# Main.net
KiCad netlist of a schematic drawn in Altium Designer
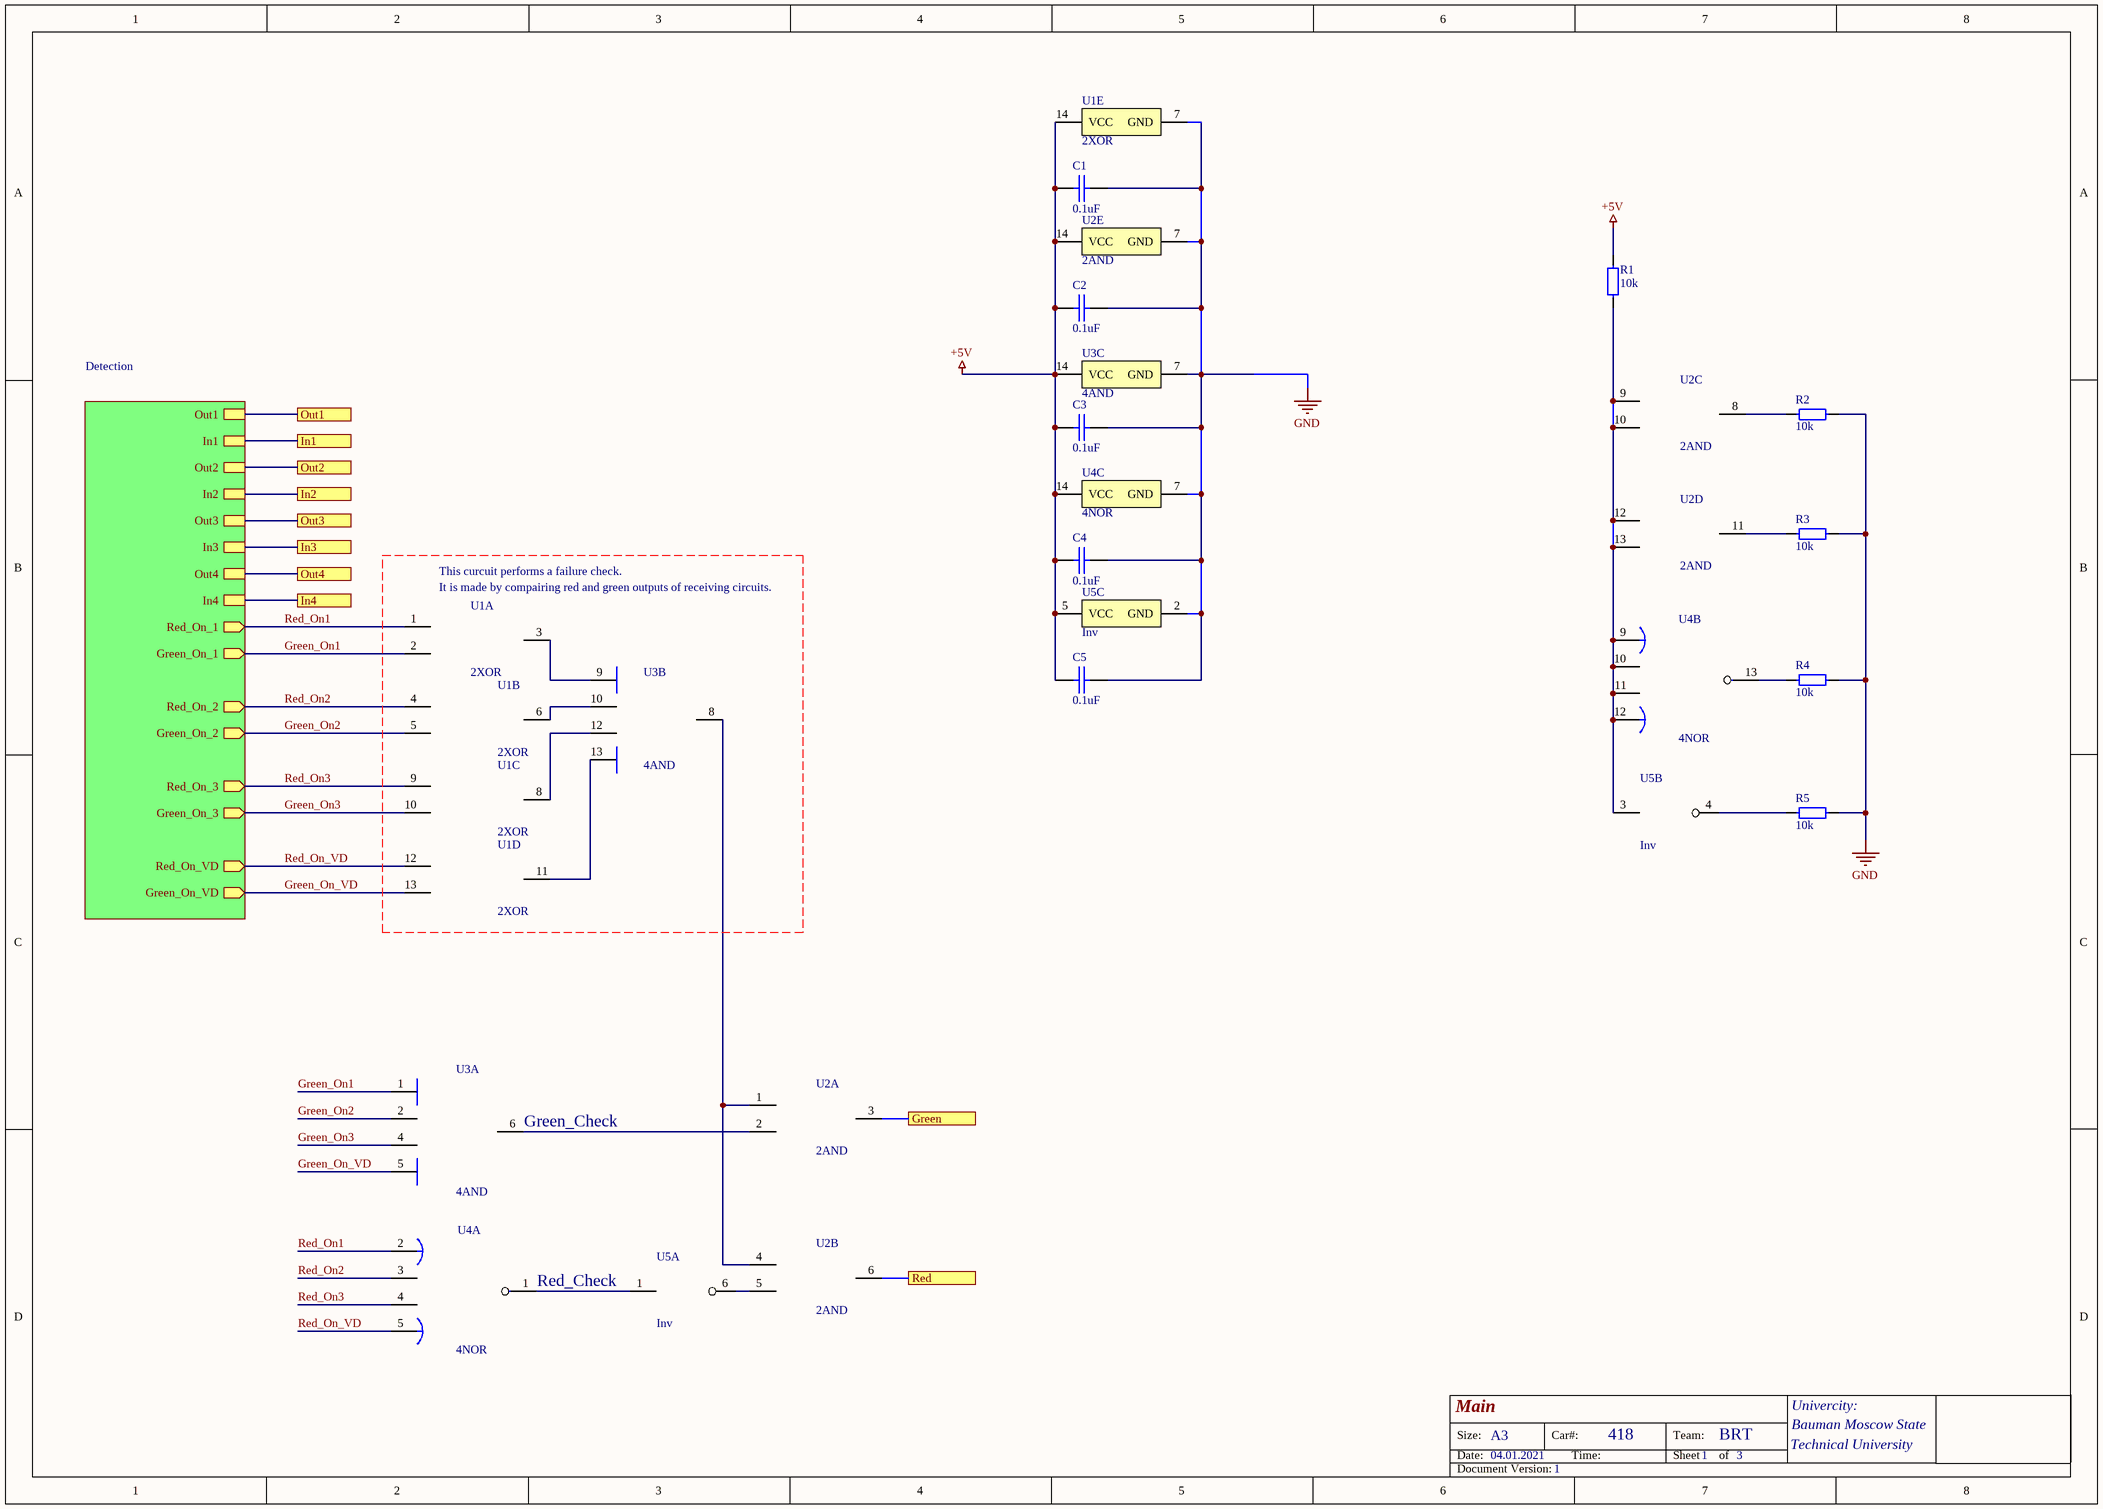
[diagram p0: Main.SchDoc]

(export (version "E")
  (design (tool "Eeschema 10.0.6"))
  (components
    (comp (ref "C1")
      (value "0.1uF")
      (footprint "0603 Capicator")
      (description "0.1uF X7R 16V 10% 0603")
      (fields
        (field (name "MANUFACTURER") "Murata Manufacturing")
        (field (name "PART NUMBER") "GRM188R71C104KA01D")
      )
      (libsource (lib "BRT_Components") (part "Cap 0.1uF (0603)"))
    )
    (comp (ref "C2")
      (value "0.1uF")
      (footprint "0603 Capicator")
      (description "0.1uF X7R 16V 10% 0603")
      (fields
        (field (name "MANUFACTURER") "Murata Manufacturing")
        (field (name "PART NUMBER") "GRM188R71C104KA01D")
      )
      (libsource (lib "BRT_Components") (part "Cap 0.1uF (0603)"))
    )
    (comp (ref "C3")
      (value "0.1uF")
      (footprint "0603 Capicator")
      (description "0.1uF X7R 16V 10% 0603")
      (fields
        (field (name "MANUFACTURER") "Murata Manufacturing")
        (field (name "PART NUMBER") "GRM188R71C104KA01D")
      )
      (libsource (lib "BRT_Components") (part "Cap 0.1uF (0603)"))
    )
    (comp (ref "C4")
      (value "0.1uF")
      (footprint "0603 Capicator")
      (description "0.1uF X7R 16V 10% 0603")
      (fields
        (field (name "MANUFACTURER") "Murata Manufacturing")
        (field (name "PART NUMBER") "GRM188R71C104KA01D")
      )
      (libsource (lib "BRT_Components") (part "Cap 0.1uF (0603)"))
    )
    (comp (ref "C5")
      (value "0.1uF")
      (footprint "0603 Capicator")
      (description "0.1uF X7R 16V 10% 0603")
      (fields
        (field (name "MANUFACTURER") "Murata Manufacturing")
        (field (name "PART NUMBER") "GRM188R71C104KA01D")
      )
      (libsource (lib "BRT_Components") (part "Cap 0.1uF (0603)"))
    )
    (comp (ref "R1")
      (value "10k")
      (footprint "0603 Resistor")
      (description "0.1W 0603 10k, 1%")
      (fields (field (name "PART NUMBER") "RC0603FR-0710KL") (field (name "MANUFACTURER") "Taiwan"))
      (libsource (lib "BRT_Components") (part "Res 10k (0603)"))
    )
    (comp (ref "R2")
      (value "10k")
      (footprint "0603 Resistor")
      (description "0.1W 0603 10k, 1%")
      (fields (field (name "PART NUMBER") "RC0603FR-0710KL") (field (name "MANUFACTURER") "Taiwan"))
      (libsource (lib "BRT_Components") (part "Res 10k (0603)"))
    )
    (comp (ref "R3")
      (value "10k")
      (footprint "0603 Resistor")
      (description "0.1W 0603 10k, 1%")
      (fields (field (name "PART NUMBER") "RC0603FR-0710KL") (field (name "MANUFACTURER") "Taiwan"))
      (libsource (lib "BRT_Components") (part "Res 10k (0603)"))
    )
    (comp (ref "R4")
      (value "10k")
      (footprint "0603 Resistor")
      (description "0.1W 0603 10k, 1%")
      (fields (field (name "PART NUMBER") "RC0603FR-0710KL") (field (name "MANUFACTURER") "Taiwan"))
      (libsource (lib "BRT_Components") (part "Res 10k (0603)"))
    )
    (comp (ref "R5")
      (value "10k")
      (footprint "0603 Resistor")
      (description "0.1W 0603 10k, 1%")
      (fields (field (name "PART NUMBER") "RC0603FR-0710KL") (field (name "MANUFACTURER") "Taiwan"))
      (libsource (lib "BRT_Components") (part "Res 10k (0603)"))
    )
    (comp (ref "U1")
      (value "2XOR")
      (footprint "SOIC-14")
      (description "4 logic elements \"2XOR\"")
      (fields (field (name "PART NUMBER") "74HC86D,653") (field (name "MANUFACTURER") "Nexperia"))
      (libsource (lib "BRT_Components") (part "4(2XOR)"))
    )
    (comp (ref "U2")
      (value "2AND")
      (footprint "SOIC-14")
      (description "4 logic elements \"2AND\"")
      (fields (field (name "PART NUMBER") "SN74AC08DR") (field (name "MANUFACTURER") "Texas Instruments"))
      (libsource (lib "BRT_Components") (part "2And"))
    )
    (comp (ref "U3")
      (value "4AND")
      (footprint "SOIC-14")
      (description "2 logic elements \"4AND\"")
      (fields (field (name "PART NUMBER") "74HC21D,653") (field (name "MANUFACTURER") "Nexperia"))
      (libsource (lib "BRT_Components") (part "2(4AND)"))
    )
    (comp (ref "U4")
      (value "4NOR")
      (footprint "SOIC-14")
      (description "2 logic elements \"4NOR\"")
      (fields (field (name "PART NUMBER") "74HC4002D,652") (field (name "MANUFACTURER") "Nexperia"))
      (libsource (lib "BRT_Components") (part "2(4NOR)"))
    )
    (comp (ref "U5")
      (value "Inv")
      (footprint "SOT236")
      (description "Dual inverter, 1.65-5.5V")
      (fields
        (field (name "MANUFACTURER") "Texas Instruments")
        (field (name "PART NUMBER") "SN74LVC2G04DBVR")
      )
      (libsource (lib "BRT_Components") (part "Inverter (SN74)"))
    )
  )
  (nets
    (net (code "1") (name "+5V") (class "Default")
      (node (ref "C1") (pin "2") (pinfunction "2_2") (pintype "passive"))
      (node (ref "C2") (pin "2") (pinfunction "2_2") (pintype "passive"))
      (node (ref "C3") (pin "2") (pinfunction "2_2") (pintype "passive"))
      (node (ref "C4") (pin "2") (pinfunction "2_2") (pintype "passive"))
      (node (ref "C5") (pin "2") (pinfunction "2_2") (pintype "passive"))
      (node (ref "R1") (pin "2") (pinfunction "2_2") (pintype "passive"))
      (node (ref "U1") (pin "14") (pinfunction "VCC_14") (pintype "passive"))
      (node (ref "U2") (pin "14") (pinfunction "VCC_14") (pintype "power_in"))
      (node (ref "U3") (pin "14") (pinfunction "VCC_14") (pintype "passive"))
      (node (ref "U4") (pin "14") (pinfunction "VCC_14") (pintype "passive"))
      (node (ref "U5") (pin "5") (pinfunction "VCC_5") (pintype "power_in"))
    )
    (net (code "2") (name "/Green") (class "Default")
      (node (ref "U2") (pin "3") (pinfunction "1Y_3") (pintype "passive"))
    )
    (net (code "3") (name "/Green_On1") (class "Default")
      (node (ref "U1") (pin "2") (pinfunction "B_2") (pintype "passive"))
      (node (ref "U3") (pin "1") (pinfunction "A_1") (pintype "passive"))
    )
    (net (code "4") (name "/Green_On2") (class "Default")
      (node (ref "U1") (pin "5") (pinfunction "B_5") (pintype "passive"))
      (node (ref "U3") (pin "2") (pinfunction "B_2") (pintype "passive"))
    )
    (net (code "5") (name "/Green_On3") (class "Default")
      (node (ref "U1") (pin "10") (pinfunction "B_10") (pintype "passive"))
      (node (ref "U3") (pin "4") (pinfunction "C_4") (pintype "passive"))
    )
    (net (code "6") (name "/Green_On_VD") (class "Default")
      (node (ref "U1") (pin "13") (pinfunction "B_13") (pintype "passive"))
      (node (ref "U3") (pin "5") (pinfunction "D_5") (pintype "passive"))
    )
    (net (code "15") (name "/Red") (class "Default")
      (node (ref "U2") (pin "6") (pinfunction "2Y_6") (pintype "passive"))
    )
    (net (code "16") (name "/Red_On1") (class "Default")
      (node (ref "U1") (pin "1") (pinfunction "A_1") (pintype "passive"))
      (node (ref "U4") (pin "2") (pinfunction "A_2") (pintype "passive"))
    )
    (net (code "17") (name "/Red_On2") (class "Default")
      (node (ref "U1") (pin "4") (pinfunction "A_4") (pintype "passive"))
      (node (ref "U4") (pin "3") (pinfunction "B_3") (pintype "passive"))
    )
    (net (code "18") (name "/Red_On3") (class "Default")
      (node (ref "U1") (pin "9") (pinfunction "A_9") (pintype "passive"))
      (node (ref "U4") (pin "4") (pinfunction "C_4") (pintype "passive"))
    )
    (net (code "19") (name "/Red_On_VD") (class "Default")
      (node (ref "U1") (pin "12") (pinfunction "A_12") (pintype "passive"))
      (node (ref "U4") (pin "5") (pinfunction "D_5") (pintype "passive"))
    )
    (net (code "20") (name "GND") (class "Default")
      (node (ref "C1") (pin "1") (pinfunction "1_1") (pintype "passive"))
      (node (ref "C2") (pin "1") (pinfunction "1_1") (pintype "passive"))
      (node (ref "C3") (pin "1") (pinfunction "1_1") (pintype "passive"))
      (node (ref "C4") (pin "1") (pinfunction "1_1") (pintype "passive"))
      (node (ref "C5") (pin "1") (pinfunction "1_1") (pintype "passive"))
      (node (ref "R2") (pin "1") (pinfunction "1_1") (pintype "passive"))
      (node (ref "R3") (pin "1") (pinfunction "1_1") (pintype "passive"))
      (node (ref "R4") (pin "1") (pinfunction "1_1") (pintype "passive"))
      (node (ref "R5") (pin "1") (pinfunction "1_1") (pintype "passive"))
      (node (ref "U1") (pin "7") (pinfunction "GND_7") (pintype "passive"))
      (node (ref "U2") (pin "7") (pinfunction "GND_7") (pintype "power_in"))
      (node (ref "U3") (pin "7") (pinfunction "GND_7") (pintype "passive"))
      (node (ref "U4") (pin "7") (pinfunction "GND_7") (pintype "passive"))
      (node (ref "U5") (pin "2") (pinfunction "GND_2") (pintype "power_in"))
    )
    (net (code "21") (name "Net-(U1A-Y)") (class "Default")
      (node (ref "U1") (pin "3") (pinfunction "Y_3") (pintype "passive"))
      (node (ref "U3") (pin "9") (pinfunction "A_9") (pintype "passive"))
    )
    (net (code "22") (name "Net-(U1B-Y)") (class "Default")
      (node (ref "U1") (pin "6") (pinfunction "Y_6") (pintype "passive"))
      (node (ref "U3") (pin "10") (pinfunction "B_10") (pintype "passive"))
    )
    (net (code "23") (name "Net-(U1C-Y)") (class "Default")
      (node (ref "U1") (pin "8") (pinfunction "Y_8") (pintype "passive"))
      (node (ref "U3") (pin "12") (pinfunction "C_12") (pintype "passive"))
    )
    (net (code "24") (name "Net-(U1D-Y)") (class "Default")
      (node (ref "U1") (pin "11") (pinfunction "Y_11") (pintype "passive"))
      (node (ref "U3") (pin "13") (pinfunction "D_13") (pintype "passive"))
    )
    (net (code "25") (name "Net-(U2A-1A)") (class "Default")
      (node (ref "U2") (pin "1") (pinfunction "1A_1") (pintype "passive"))
      (node (ref "U2") (pin "4") (pinfunction "2A_4") (pintype "passive"))
      (node (ref "U3") (pin "8") (pinfunction "Y_8") (pintype "passive"))
    )
    (net (code "26") (name "Net-(U2A-1B)") (class "Default")
      (node (ref "U2") (pin "2") (pinfunction "1B_2") (pintype "passive"))
      (node (ref "U3") (pin "6") (pinfunction "Y_6") (pintype "passive"))
    )
    (net (code "27") (name "Net-(U2B-2B)") (class "Default")
      (node (ref "U2") (pin "5") (pinfunction "2B_5") (pintype "passive"))
      (node (ref "U5") (pin "6") (pinfunction "1Y_6") (pintype "passive"))
    )
    (net (code "28") (name "Net-(U2C-3A)") (class "Default")
      (node (ref "R1") (pin "1") (pinfunction "1_1") (pintype "passive"))
      (node (ref "U2") (pin "10") (pinfunction "3B_10") (pintype "passive"))
      (node (ref "U2") (pin "12") (pinfunction "4A_12") (pintype "passive"))
      (node (ref "U2") (pin "13") (pinfunction "4B_13") (pintype "passive"))
      (node (ref "U2") (pin "9") (pinfunction "3A_9") (pintype "passive"))
      (node (ref "U4") (pin "10") (pinfunction "B_10") (pintype "passive"))
      (node (ref "U4") (pin "11") (pinfunction "C_11") (pintype "passive"))
      (node (ref "U4") (pin "12") (pinfunction "D_12") (pintype "passive"))
      (node (ref "U4") (pin "9") (pinfunction "A_9") (pintype "passive"))
      (node (ref "U5") (pin "3") (pinfunction "2А_3") (pintype "passive"))
    )
    (net (code "29") (name "Net-(U2C-3Y)") (class "Default")
      (node (ref "R2") (pin "2") (pinfunction "2_2") (pintype "passive"))
      (node (ref "U2") (pin "8") (pinfunction "3Y_8") (pintype "passive"))
    )
    (net (code "30") (name "Net-(U2D-4Y)") (class "Default")
      (node (ref "R3") (pin "2") (pinfunction "2_2") (pintype "passive"))
      (node (ref "U2") (pin "11") (pinfunction "4Y_11") (pintype "passive"))
    )
    (net (code "31") (name "Net-(U4A-Y)") (class "Default")
      (node (ref "U4") (pin "1") (pinfunction "Y_1") (pintype "passive"))
      (node (ref "U5") (pin "1") (pinfunction "1A_1") (pintype "passive"))
    )
    (net (code "32") (name "Net-(U4B-Y)") (class "Default")
      (node (ref "R4") (pin "2") (pinfunction "2_2") (pintype "passive"))
      (node (ref "U4") (pin "13") (pinfunction "Y_13") (pintype "passive"))
    )
    (net (code "33") (name "Net-(U5B-2Y)") (class "Default")
      (node (ref "R5") (pin "2") (pinfunction "2_2") (pintype "passive"))
      (node (ref "U5") (pin "4") (pinfunction "2Y_4") (pintype "passive"))
    )
  )
)
